# ReboostV2_USB.net
KiCad netlist of a schematic drawn in Altium Designer
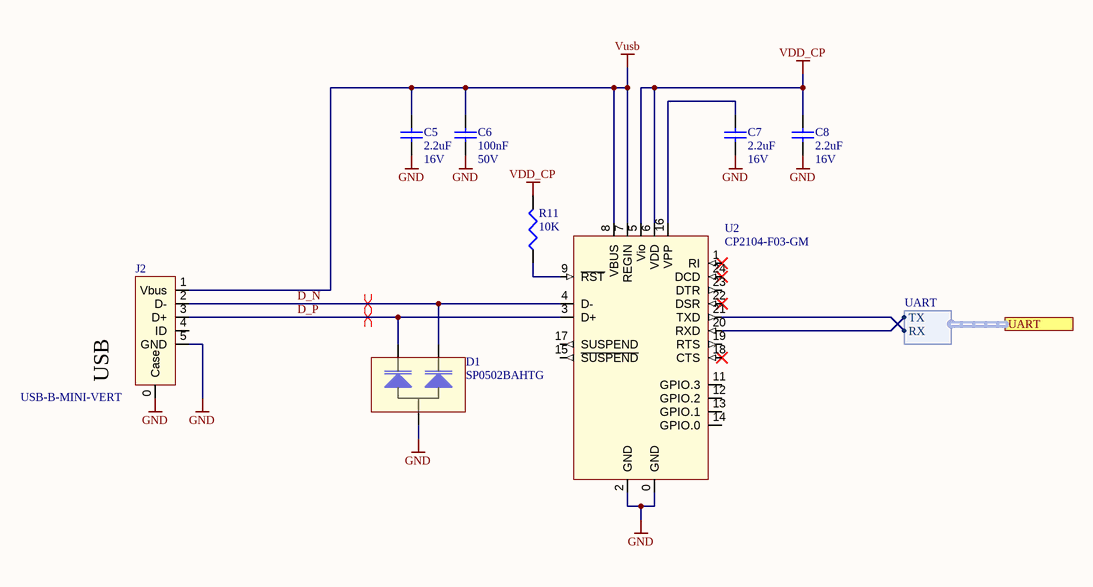
[diagram p0: ReboostV2_USB.SchDoc]

(export (version "E")
  (design (tool "Eeschema 10.0.6"))
  (components
    (comp (ref "C5")
      (value "2.2uF")
      (footprint "C0603")
      (description "Capacitor, 2.2uF, 16V, X5R")
      (fields (field (name "VOLTAGE RATING") "16V"))
      (libsource (lib "AR_Capacitors_Ceramic") (part "2.2uF/0603/CER/16V"))
    )
    (comp (ref "C6")
      (value "100nF")
      (footprint "C0603")
      (description "Capacitor, 100nF, 50V, X7R")
      (fields (field (name "VOLTAGE RATING") "50V"))
      (libsource (lib "AR_Capacitors_Ceramic") (part "100nF/0603/CER/50V"))
    )
    (comp (ref "C7")
      (value "2.2uF")
      (footprint "C0603")
      (description "Capacitor, 2.2uF, 16V, X5R")
      (fields (field (name "VOLTAGE RATING") "16V"))
      (libsource (lib "AR_Capacitors_Ceramic") (part "2.2uF/0603/CER/16V"))
    )
    (comp (ref "C8")
      (value "2.2uF")
      (footprint "C0603")
      (description "Capacitor, 2.2uF, 16V, X5R")
      (fields (field (name "VOLTAGE RATING") "16V"))
      (libsource (lib "AR_Capacitors_Ceramic") (part "2.2uF/0603/CER/16V"))
    )
    (comp (ref "D1")
      (value "SP0502BAHTG")
      (footprint "SOT23")
      (description "Diode TVS Dual, Vrwm: 5.5V Vc: 8V")
      (libsource (lib "AR_Diodes") (part "SP0502BAHTG"))
    )
    (comp (ref "J2")
      (value "USB-B-MINI-VERT")
      (footprint "USB-B-MINI-VERT")
      (description "Connector, Usb B Mini, Vertical, TH, WR-COM")
      (libsource (lib "AR_Connectors") (part "WE-651005136421"))
    )
    (comp (ref "R11")
      (value "10K")
      (footprint "0603")
      (description "Resistor, 10K, 1%, 0.063W, 50V, 100PPM, 0603")
      (libsource (lib "AR_Resistors_SMD") (part "10K/0603/0063W/50V"))
    )
    (comp (ref "U2")
      (value "CP2104-F03-GM")
      (footprint "QFN24")
      (description "USB to UART converter")
      (libsource (lib "AR_ICs") (part "CP2104-F03-GM"))
    )
  )
  (nets
    (net (code "2") (name "/D_N") (class "Default")
      (node (ref "D1") (pin "K1") (pinfunction "K1_K1") (pintype "passive"))
      (node (ref "J2") (pin "2") (pinfunction "D-_2") (pintype "passive"))
      (node (ref "U2") (pin "4") (pinfunction "D-_4") (pintype "bidirectional"))
    )
    (net (code "3") (name "/D_P") (class "Default")
      (node (ref "D1") (pin "K2") (pinfunction "K2_K2") (pintype "passive"))
      (node (ref "J2") (pin "3") (pinfunction "D+_3") (pintype "passive"))
      (node (ref "U2") (pin "3") (pinfunction "D+_3") (pintype "bidirectional"))
    )
    (net (code "4") (name "/RX") (class "Default")
      (node (ref "U2") (pin "21") (pinfunction "TXD_21") (pintype "output"))
    )
    (net (code "5") (name "/TX") (class "Default")
      (node (ref "U2") (pin "20") (pinfunction "RXD_20") (pintype "input"))
    )
    (net (code "7") (name "GND") (class "Default")
      (node (ref "C5") (pin "1") (pinfunction "1_1") (pintype "passive"))
      (node (ref "C6") (pin "1") (pinfunction "1_1") (pintype "passive"))
      (node (ref "C7") (pin "1") (pinfunction "1_1") (pintype "passive"))
      (node (ref "C8") (pin "1") (pinfunction "1_1") (pintype "passive"))
      (node (ref "D1") (pin "A") (pinfunction "A_A") (pintype "passive"))
      (node (ref "J2") (pin "0") (pinfunction "Case_0") (pintype "passive"))
      (node (ref "J2") (pin "5") (pinfunction "GND_5") (pintype "passive"))
      (node (ref "U2") (pin "0") (pinfunction "GND_0") (pintype "power_in"))
      (node (ref "U2") (pin "2") (pinfunction "GND_2") (pintype "power_in"))
    )
    (net (code "8") (name "Net-(U2-VPP)") (class "Default")
      (node (ref "C7") (pin "2") (pinfunction "2_2") (pintype "passive"))
      (node (ref "U2") (pin "16") (pinfunction "VPP_16") (pintype "power_in"))
    )
    (net (code "9") (name "Net-(U2-~{RST})") (class "Default")
      (node (ref "R11") (pin "1") (pinfunction "1_1") (pintype "passive"))
      (node (ref "U2") (pin "9") (pinfunction "~{RST}_9") (pintype "input"))
    )
    (net (code "10") (name "VDD_CP") (class "Default")
      (node (ref "C8") (pin "2") (pinfunction "2_2") (pintype "passive"))
      (node (ref "R11") (pin "2") (pinfunction "2_2") (pintype "passive"))
      (node (ref "U2") (pin "5") (pinfunction "Vio_5") (pintype "passive"))
      (node (ref "U2") (pin "6") (pinfunction "VDD_6") (pintype "power_in"))
    )
    (net (code "11") (name "Vusb") (class "Default")
      (node (ref "C5") (pin "2") (pinfunction "2_2") (pintype "passive"))
      (node (ref "C6") (pin "2") (pinfunction "2_2") (pintype "passive"))
      (node (ref "J2") (pin "1") (pinfunction "Vbus_1") (pintype "passive"))
      (node (ref "U2") (pin "7") (pinfunction "REGIN_7") (pintype "power_in"))
      (node (ref "U2") (pin "8") (pinfunction "VBUS_8") (pintype "power_in"))
    )
    (net (code "12") (name "unconnected-(J2-ID-Pad4)") (class "Default")
      (node (ref "J2") (pin "4") (pinfunction "ID_4") (pintype "passive"))
    )
    (net (code "13") (name "unconnected-(U2-CTS-Pad18)") (class "Default")
      (node (ref "U2") (pin "18") (pinfunction "CTS_18") (pintype "input+no_connect"))
    )
    (net (code "14") (name "unconnected-(U2-DCD-Pad24)") (class "Default")
      (node (ref "U2") (pin "24") (pinfunction "DCD_24") (pintype "input+no_connect"))
    )
    (net (code "15") (name "unconnected-(U2-DSR-Pad22)") (class "Default")
      (node (ref "U2") (pin "22") (pinfunction "DSR_22") (pintype "input+no_connect"))
    )
    (net (code "16") (name "unconnected-(U2-DTR-Pad23)") (class "Default")
      (node (ref "U2") (pin "23") (pinfunction "DTR_23") (pintype "output"))
    )
    (net (code "17") (name "unconnected-(U2-GPIO.0-Pad14)") (class "Default")
      (node (ref "U2") (pin "14") (pinfunction "GPIO.0_14") (pintype "passive"))
    )
    (net (code "18") (name "unconnected-(U2-GPIO.1-Pad13)") (class "Default")
      (node (ref "U2") (pin "13") (pinfunction "GPIO.1_13") (pintype "passive"))
    )
    (net (code "19") (name "unconnected-(U2-GPIO.2-Pad12)") (class "Default")
      (node (ref "U2") (pin "12") (pinfunction "GPIO.2_12") (pintype "passive"))
    )
    (net (code "20") (name "unconnected-(U2-GPIO.3-Pad11)") (class "Default")
      (node (ref "U2") (pin "11") (pinfunction "GPIO.3_11") (pintype "passive"))
    )
    (net (code "21") (name "unconnected-(U2-RI-Pad1)") (class "Default")
      (node (ref "U2") (pin "1") (pinfunction "RI_1") (pintype "input+no_connect"))
    )
    (net (code "22") (name "unconnected-(U2-RTS-Pad19)") (class "Default")
      (node (ref "U2") (pin "19") (pinfunction "RTS_19") (pintype "output"))
    )
    (net (code "23") (name "unconnected-(U2-SUSPEND-Pad17)") (class "Default")
      (node (ref "U2") (pin "17") (pinfunction "SUSPEND_17") (pintype "output"))
    )
    (net (code "24") (name "unconnected-(U2-~{SUSPEND}-Pad15)") (class "Default")
      (node (ref "U2") (pin "15") (pinfunction "~{SUSPEND}_15") (pintype "output"))
    )
  )
)
